# EMG_Final.net
KiCad netlist of a schematic drawn in EAGLE
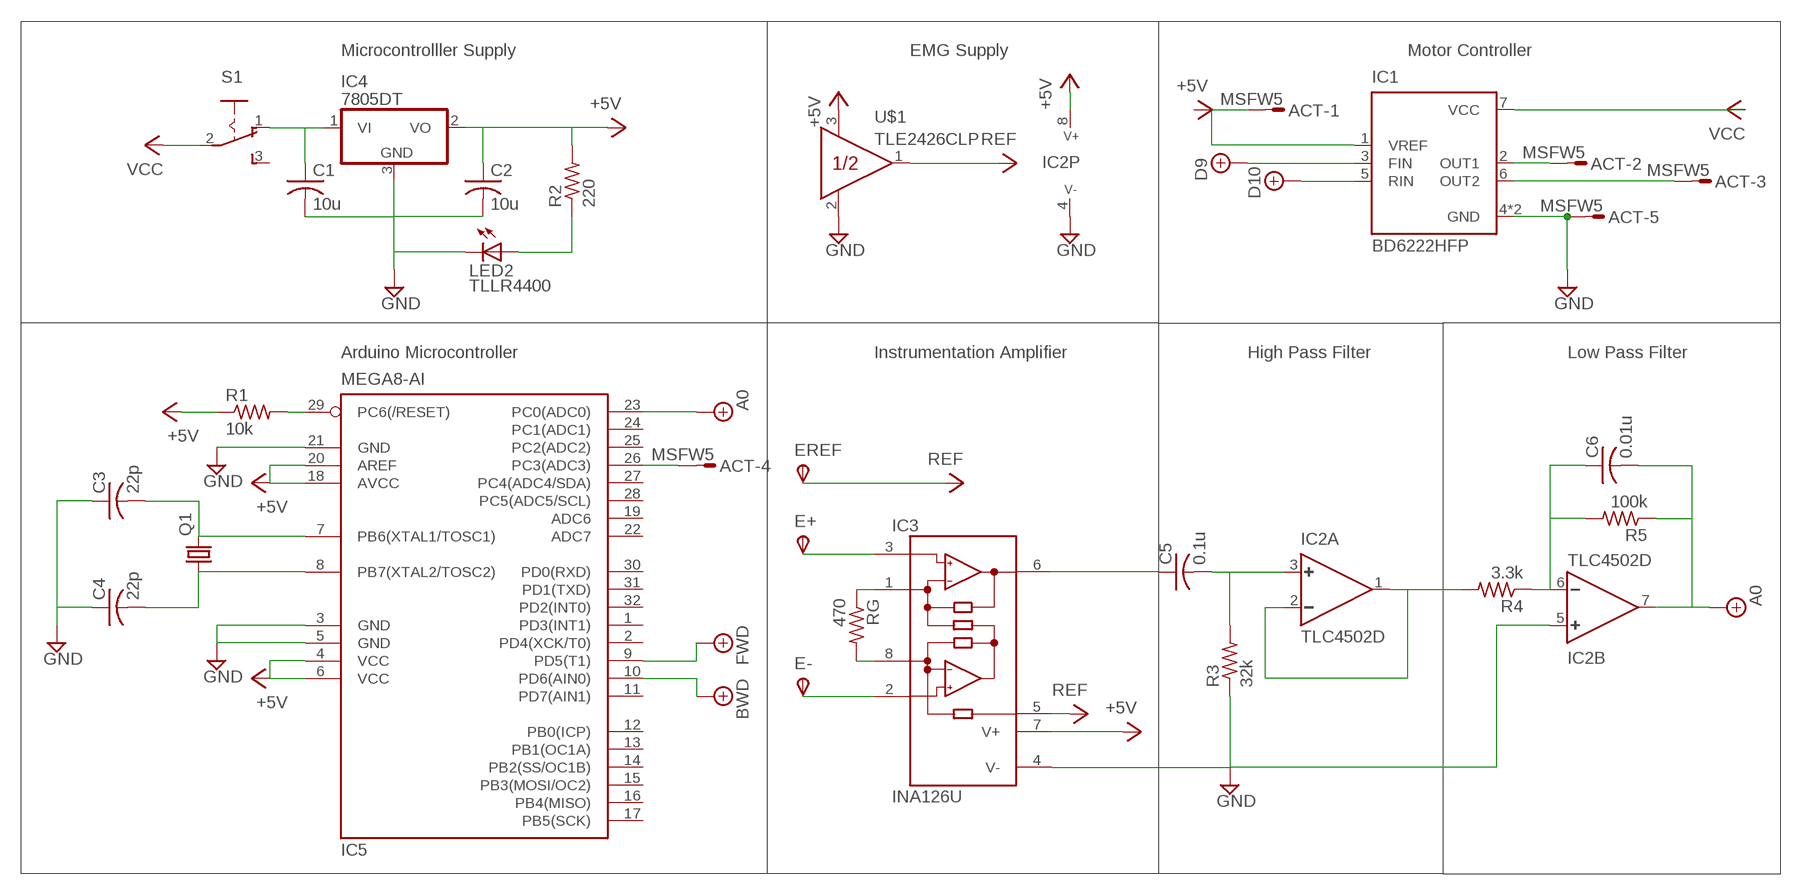
[diagram p0: schematic, sheet 1]

(export (version "E")
  (design (tool "Eeschema 10.0.6"))
  (components
    (comp (ref "ACT")
      (value "MSFW5")
      (footprint "eagle-import:MSFW5")
      (libsource (lib "eagle-import") (part "MSFW5"))
    )
    (comp (ref "C1")
      (value "10u")
      (footprint "eagle-import:C0603")
      (libsource (lib "eagle-import") (part "C-USC0603"))
    )
    (comp (ref "C2")
      (value "10u")
      (footprint "eagle-import:C0603")
      (libsource (lib "eagle-import") (part "C-USC0603"))
    )
    (comp (ref "C3")
      (value "22p")
      (footprint "eagle-import:C0603")
      (libsource (lib "eagle-import") (part "C-USC0603"))
    )
    (comp (ref "C4")
      (value "22p")
      (footprint "eagle-import:C0603")
      (libsource (lib "eagle-import") (part "C-USC0603"))
    )
    (comp (ref "C5")
      (value "0.1u")
      (footprint "eagle-import:C0603")
      (libsource (lib "eagle-import") (part "C-USC0603"))
    )
    (comp (ref "C6")
      (value "0.01u")
      (footprint "eagle-import:C0603")
      (libsource (lib "eagle-import") (part "C-USC0603"))
    )
    (comp (ref "E+")
      (value "TPSPAD1-13")
      (footprint "eagle-import:P1-13")
      (libsource (lib "eagle-import") (part "TPSPAD1-13"))
    )
    (comp (ref "E-")
      (value "TPSPAD1-13")
      (footprint "eagle-import:P1-13")
      (libsource (lib "eagle-import") (part "TPSPAD1-13"))
    )
    (comp (ref "EREF")
      (value "TPSPAD1-13")
      (footprint "eagle-import:P1-13")
      (libsource (lib "eagle-import") (part "TPSPAD1-13"))
    )
    (comp (ref "IC1")
      (value "BD6222HFP")
      (footprint "eagle-import:HRP7")
      (libsource (lib "eagle-import") (part "BD622HFP2"))
    )
    (comp (ref "IC2")
      (value "TLC4502D")
      (footprint "eagle-import:D_R-PDSO-G08")
      (libsource (lib "eagle-import") (part "TLC4502D"))
    )
    (comp (ref "IC3")
      (value "INA126U")
      (footprint "eagle-import:SO08")
      (fields (field (name "MF") "TEXAS INSTRUMENTS"))
      (libsource (lib "eagle-import") (part "INA126U"))
    )
    (comp (ref "IC4")
      (value "7805DT")
      (footprint "eagle-import:TO252")
      (libsource (lib "eagle-import") (part "78DT05"))
    )
    (comp (ref "IC5")
      (value "MEGA8-AI")
      (footprint "eagle-import:TQFP32-08")
      (fields (field (name "MPN") "ATMEGA8-16AU"))
      (libsource (lib "eagle-import") (part "MEGA8-AI"))
    )
    (comp (ref "LED2")
      (value "TLLR4400")
      (footprint "eagle-import:LED3MM")
      (fields (field (name "MF") "VISHAY SEMICONDUCTOR"))
      (libsource (lib "eagle-import") (part "TLLR4400"))
    )
    (comp (ref "Q1")
      (value "CRYSTALMM20SS")
      (footprint "eagle-import:MM20SS")
      (libsource (lib "eagle-import") (part "CRYSTALMM20SS"))
    )
    (comp (ref "R1")
      (value "10k")
      (footprint "eagle-import:R0603")
      (libsource (lib "eagle-import") (part "R-US_R0603"))
    )
    (comp (ref "R2")
      (value "220")
      (footprint "eagle-import:R0603")
      (libsource (lib "eagle-import") (part "R-US_R0603"))
    )
    (comp (ref "R3")
      (value "32k")
      (footprint "eagle-import:R0603")
      (libsource (lib "eagle-import") (part "R-US_R0603"))
    )
    (comp (ref "R4")
      (value "3.3k")
      (footprint "eagle-import:R0603")
      (libsource (lib "eagle-import") (part "R-US_R0603"))
    )
    (comp (ref "R5")
      (value "100k")
      (footprint "eagle-import:R0603")
      (libsource (lib "eagle-import") (part "R-US_R0603"))
    )
    (comp (ref "RG")
      (value "470")
      (footprint "eagle-import:R0603")
      (libsource (lib "eagle-import") (part "R-US_R0603"))
    )
    (comp (ref "S1")
      (value "255SB")
      (footprint "eagle-import:255SB")
      (libsource (lib "eagle-import") (part "255SB"))
    )
    (comp (ref "U$1")
      (value "TLE2426CLP")
      (footprint "eagle-import:TO226AA")
      (libsource (lib "eagle-import") (part "TLE2426LPC"))
    )
  )
  (nets
    (net (code "1") (name "+5V") (class "Default")
      (node (ref "C2") (pin "1") (pinfunction "1_1") (pintype "passive"))
      (node (ref "IC2") (pin "8") (pinfunction "V+_8") (pintype "power_in"))
      (node (ref "IC3") (pin "7") (pinfunction "V+_7") (pintype "power_in"))
      (node (ref "IC4") (pin "2") (pinfunction "VO_2") (pintype "passive"))
      (node (ref "IC5") (pin "18") (pinfunction "AVCC_18") (pintype "power_in"))
      (node (ref "IC5") (pin "20") (pinfunction "AREF_20") (pintype "passive"))
      (node (ref "IC5") (pin "4") (pinfunction "VCC_4") (pintype "power_in"))
      (node (ref "IC5") (pin "6") (pinfunction "VCC_6") (pintype "power_in"))
      (node (ref "R1") (pin "1") (pinfunction "1_1") (pintype "passive"))
      (node (ref "R2") (pin "2") (pinfunction "2_2") (pintype "passive"))
      (node (ref "U$1") (pin "3") (pinfunction "IN_3") (pintype "passive"))
    )
    (net (code "2") (name "A0") (class "Default")
      (node (ref "C6") (pin "2") (pinfunction "2_2") (pintype "passive"))
      (node (ref "IC2") (pin "7") (pinfunction "OUT_7") (pintype "output"))
      (node (ref "IC5") (pin "23") (pinfunction "PC0(ADC0)_23") (pintype "bidirectional"))
      (node (ref "R5") (pin "1") (pinfunction "1_1") (pintype "passive"))
    )
    (net (code "3") (name "BWD") (class "Default")
      (node (ref "IC1") (pin "5") (pinfunction "RIN_5") (pintype "input"))
      (node (ref "IC5") (pin "10") (pinfunction "PD6(AIN0)_10") (pintype "bidirectional"))
    )
    (net (code "4") (name "D9") (class "Default")
      (node (ref "IC1") (pin "3") (pinfunction "FIN_3") (pintype "input"))
      (node (ref "IC5") (pin "9") (pinfunction "PD5(T1)_9") (pintype "bidirectional"))
    )
    (net (code "5") (name "GND") (class "Default")
      (node (ref "ACT") (pin "5") (pinfunction "S_5") (pintype "passive"))
      (node (ref "C1") (pin "2") (pinfunction "2_2") (pintype "passive"))
      (node (ref "C2") (pin "2") (pinfunction "2_2") (pintype "passive"))
      (node (ref "C3") (pin "1") (pinfunction "1_1") (pintype "passive"))
      (node (ref "C4") (pin "1") (pinfunction "1_1") (pintype "passive"))
      (node (ref "IC1") (pin "4") (pinfunction "GND_4") (pintype "power_in"))
      (node (ref "IC1") (pin "P") (pinfunction "GND_P") (pintype "power_in"))
      (node (ref "IC2") (pin "4") (pinfunction "V-_4") (pintype "power_in"))
      (node (ref "IC2") (pin "5") (pinfunction "+_5") (pintype "input"))
      (node (ref "IC3") (pin "4") (pinfunction "V-_4") (pintype "power_in"))
      (node (ref "IC4") (pin "3") (pinfunction "GND_3") (pintype "passive"))
      (node (ref "IC5") (pin "21") (pinfunction "GND_21") (pintype "power_in"))
      (node (ref "IC5") (pin "3") (pinfunction "GND_3") (pintype "power_in"))
      (node (ref "IC5") (pin "5") (pinfunction "GND_5") (pintype "power_in"))
      (node (ref "LED2") (pin "K") (pinfunction "C_K") (pintype "passive"))
      (node (ref "R3") (pin "1") (pinfunction "1_1") (pintype "passive"))
      (node (ref "U$1") (pin "2") (pinfunction "COM_2") (pintype "passive"))
    )
    (net (code "6") (name "Net-(ACTA-S)") (class "Default")
      (node (ref "ACT") (pin "1") (pinfunction "S_1") (pintype "passive"))
      (node (ref "IC1") (pin "1") (pinfunction "VREF_1") (pintype "passive"))
    )
    (net (code "7") (name "Net-(ACTB-S)") (class "Default")
      (node (ref "ACT") (pin "2") (pinfunction "S_2") (pintype "passive"))
      (node (ref "IC1") (pin "2") (pinfunction "OUT1_2") (pintype "output"))
    )
    (net (code "8") (name "Net-(ACTC-S)") (class "Default")
      (node (ref "ACT") (pin "3") (pinfunction "S_3") (pintype "passive"))
      (node (ref "IC1") (pin "6") (pinfunction "OUT2_6") (pintype "output"))
    )
    (net (code "9") (name "Net-(ACTD-S)") (class "Default")
      (node (ref "ACT") (pin "4") (pinfunction "S_4") (pintype "passive"))
      (node (ref "IC5") (pin "26") (pinfunction "PC3(ADC3)_26") (pintype "bidirectional"))
    )
    (net (code "10") (name "Net-(E+-PP)") (class "Default")
      (node (ref "E+") (pin "TP") (pinfunction "PP_TP") (pintype "input"))
      (node (ref "IC3") (pin "3") (pinfunction "+IN_3") (pintype "input"))
    )
    (net (code "11") (name "Net-(E--PP)") (class "Default")
      (node (ref "E-") (pin "TP") (pinfunction "PP_TP") (pintype "input"))
      (node (ref "IC3") (pin "2") (pinfunction "-IN_2") (pintype "input"))
    )
    (net (code "12") (name "Net-(IC2A-+)") (class "Default")
      (node (ref "C5") (pin "2") (pinfunction "2_2") (pintype "passive"))
      (node (ref "IC2") (pin "3") (pinfunction "+_3") (pintype "input"))
      (node (ref "R3") (pin "2") (pinfunction "2_2") (pintype "passive"))
    )
    (net (code "13") (name "Net-(IC2A--)") (class "Default")
      (node (ref "IC2") (pin "1") (pinfunction "OUT_1") (pintype "output"))
      (node (ref "IC2") (pin "2") (pinfunction "-_2") (pintype "input"))
      (node (ref "R4") (pin "2") (pinfunction "2_2") (pintype "passive"))
    )
    (net (code "14") (name "Net-(IC2B--)") (class "Default")
      (node (ref "C6") (pin "1") (pinfunction "1_1") (pintype "passive"))
      (node (ref "IC2") (pin "6") (pinfunction "-_6") (pintype "input"))
      (node (ref "R4") (pin "1") (pinfunction "1_1") (pintype "passive"))
      (node (ref "R5") (pin "2") (pinfunction "2_2") (pintype "passive"))
    )
    (net (code "15") (name "Net-(IC3-OUT)") (class "Default")
      (node (ref "C5") (pin "1") (pinfunction "1_1") (pintype "passive"))
      (node (ref "IC3") (pin "6") (pinfunction "OUT_6") (pintype "output"))
    )
    (net (code "16") (name "Net-(IC3-RG-Pad1)") (class "Default")
      (node (ref "IC3") (pin "1") (pinfunction "RG_1") (pintype "passive"))
      (node (ref "RG") (pin "1") (pinfunction "1_1") (pintype "passive"))
    )
    (net (code "17") (name "Net-(IC3-RG-Pad8)") (class "Default")
      (node (ref "IC3") (pin "8") (pinfunction "RG_8") (pintype "passive"))
      (node (ref "RG") (pin "2") (pinfunction "2_2") (pintype "passive"))
    )
    (net (code "18") (name "Net-(IC4-VI)") (class "Default")
      (node (ref "C1") (pin "1") (pinfunction "1_1") (pintype "passive"))
      (node (ref "IC4") (pin "1") (pinfunction "VI_1") (pintype "input"))
      (node (ref "S1") (pin "1") (pinfunction "O_1") (pintype "passive"))
    )
    (net (code "19") (name "Net-(IC5-PB6(XTAL1{slash}TOSC1))") (class "Default")
      (node (ref "C3") (pin "2") (pinfunction "2_2") (pintype "passive"))
      (node (ref "IC5") (pin "7") (pinfunction "PB6(XTAL1/TOSC1)_7") (pintype "bidirectional"))
      (node (ref "Q1") (pin "4") (pinfunction "2_4") (pintype "passive"))
    )
    (net (code "20") (name "Net-(IC5-PB7(XTAL2{slash}TOSC2))") (class "Default")
      (node (ref "C4") (pin "2") (pinfunction "2_2") (pintype "passive"))
      (node (ref "IC5") (pin "8") (pinfunction "PB7(XTAL2/TOSC2)_8") (pintype "bidirectional"))
      (node (ref "Q1") (pin "1") (pinfunction "1_1") (pintype "passive"))
    )
    (net (code "21") (name "Net-(IC5-PC6({slash}RESET))") (class "Default")
      (node (ref "IC5") (pin "29") (pinfunction "PC6(/RESET)_29") (pintype "bidirectional"))
      (node (ref "R1") (pin "2") (pinfunction "2_2") (pintype "passive"))
    )
    (net (code "22") (name "Net-(LED2-PadA)") (class "Default")
      (node (ref "LED2") (pin "A") (pinfunction "A_A") (pintype "passive"))
      (node (ref "R2") (pin "1") (pinfunction "1_1") (pintype "passive"))
    )
    (net (code "23") (name "REF") (class "Default")
      (node (ref "EREF") (pin "TP") (pinfunction "PP_TP") (pintype "input"))
      (node (ref "IC3") (pin "5") (pinfunction "REF_5") (pintype "passive"))
      (node (ref "U$1") (pin "1") (pinfunction "OUT_1") (pintype "passive"))
    )
    (net (code "24") (name "VCC") (class "Default")
      (node (ref "IC1") (pin "7") (pinfunction "VCC_7") (pintype "power_in"))
      (node (ref "S1") (pin "2") (pinfunction "P_2") (pintype "passive"))
    )
    (net (code "25") (name "unconnected-(IC5-ADC6-Pad19)") (class "Default")
      (node (ref "IC5") (pin "19") (pinfunction "ADC6_19") (pintype "bidirectional"))
    )
    (net (code "26") (name "unconnected-(IC5-ADC7-Pad22)") (class "Default")
      (node (ref "IC5") (pin "22") (pinfunction "ADC7_22") (pintype "bidirectional"))
    )
    (net (code "27") (name "unconnected-(IC5-PB0(ICP)-Pad12)") (class "Default")
      (node (ref "IC5") (pin "12") (pinfunction "PB0(ICP)_12") (pintype "bidirectional"))
    )
    (net (code "28") (name "unconnected-(IC5-PB1(OC1A)-Pad13)") (class "Default")
      (node (ref "IC5") (pin "13") (pinfunction "PB1(OC1A)_13") (pintype "bidirectional"))
    )
    (net (code "29") (name "unconnected-(IC5-PB2(SS{slash}OC1B)-Pad14)") (class "Default")
      (node (ref "IC5") (pin "14") (pinfunction "PB2(SS/OC1B)_14") (pintype "bidirectional"))
    )
    (net (code "30") (name "unconnected-(IC5-PB3(MOSI{slash}OC2)-Pad15)") (class "Default")
      (node (ref "IC5") (pin "15") (pinfunction "PB3(MOSI/OC2)_15") (pintype "bidirectional"))
    )
    (net (code "31") (name "unconnected-(IC5-PB4(MISO)-Pad16)") (class "Default")
      (node (ref "IC5") (pin "16") (pinfunction "PB4(MISO)_16") (pintype "bidirectional"))
    )
    (net (code "32") (name "unconnected-(IC5-PB5(SCK)-Pad17)") (class "Default")
      (node (ref "IC5") (pin "17") (pinfunction "PB5(SCK)_17") (pintype "bidirectional"))
    )
    (net (code "33") (name "unconnected-(IC5-PC1(ADC1)-Pad24)") (class "Default")
      (node (ref "IC5") (pin "24") (pinfunction "PC1(ADC1)_24") (pintype "bidirectional"))
    )
    (net (code "34") (name "unconnected-(IC5-PC2(ADC2)-Pad25)") (class "Default")
      (node (ref "IC5") (pin "25") (pinfunction "PC2(ADC2)_25") (pintype "bidirectional"))
    )
    (net (code "35") (name "unconnected-(IC5-PC4(ADC4{slash}SDA)-Pad27)") (class "Default")
      (node (ref "IC5") (pin "27") (pinfunction "PC4(ADC4/SDA)_27") (pintype "bidirectional"))
    )
    (net (code "36") (name "unconnected-(IC5-PC5(ADC5{slash}SCL)-Pad28)") (class "Default")
      (node (ref "IC5") (pin "28") (pinfunction "PC5(ADC5/SCL)_28") (pintype "bidirectional"))
    )
    (net (code "37") (name "unconnected-(IC5-PD0(RXD)-Pad30)") (class "Default")
      (node (ref "IC5") (pin "30") (pinfunction "PD0(RXD)_30") (pintype "bidirectional"))
    )
    (net (code "38") (name "unconnected-(IC5-PD1(TXD)-Pad31)") (class "Default")
      (node (ref "IC5") (pin "31") (pinfunction "PD1(TXD)_31") (pintype "bidirectional"))
    )
    (net (code "39") (name "unconnected-(IC5-PD2(INT0)-Pad32)") (class "Default")
      (node (ref "IC5") (pin "32") (pinfunction "PD2(INT0)_32") (pintype "bidirectional"))
    )
    (net (code "40") (name "unconnected-(IC5-PD3(INT1)-Pad1)") (class "Default")
      (node (ref "IC5") (pin "1") (pinfunction "PD3(INT1)_1") (pintype "bidirectional"))
    )
    (net (code "41") (name "unconnected-(IC5-PD4(XCK{slash}T0)-Pad2)") (class "Default")
      (node (ref "IC5") (pin "2") (pinfunction "PD4(XCK/T0)_2") (pintype "bidirectional"))
    )
    (net (code "42") (name "unconnected-(IC5-PD7(AIN1)-Pad11)") (class "Default")
      (node (ref "IC5") (pin "11") (pinfunction "PD7(AIN1)_11") (pintype "bidirectional"))
    )
    (net (code "43") (name "unconnected-(S1-S-Pad3)") (class "Default")
      (node (ref "S1") (pin "3") (pinfunction "S_3") (pintype "passive"))
    )
  )
)
